# I2C-Level-Converter.net
KiCad netlist of a schematic drawn in EAGLE
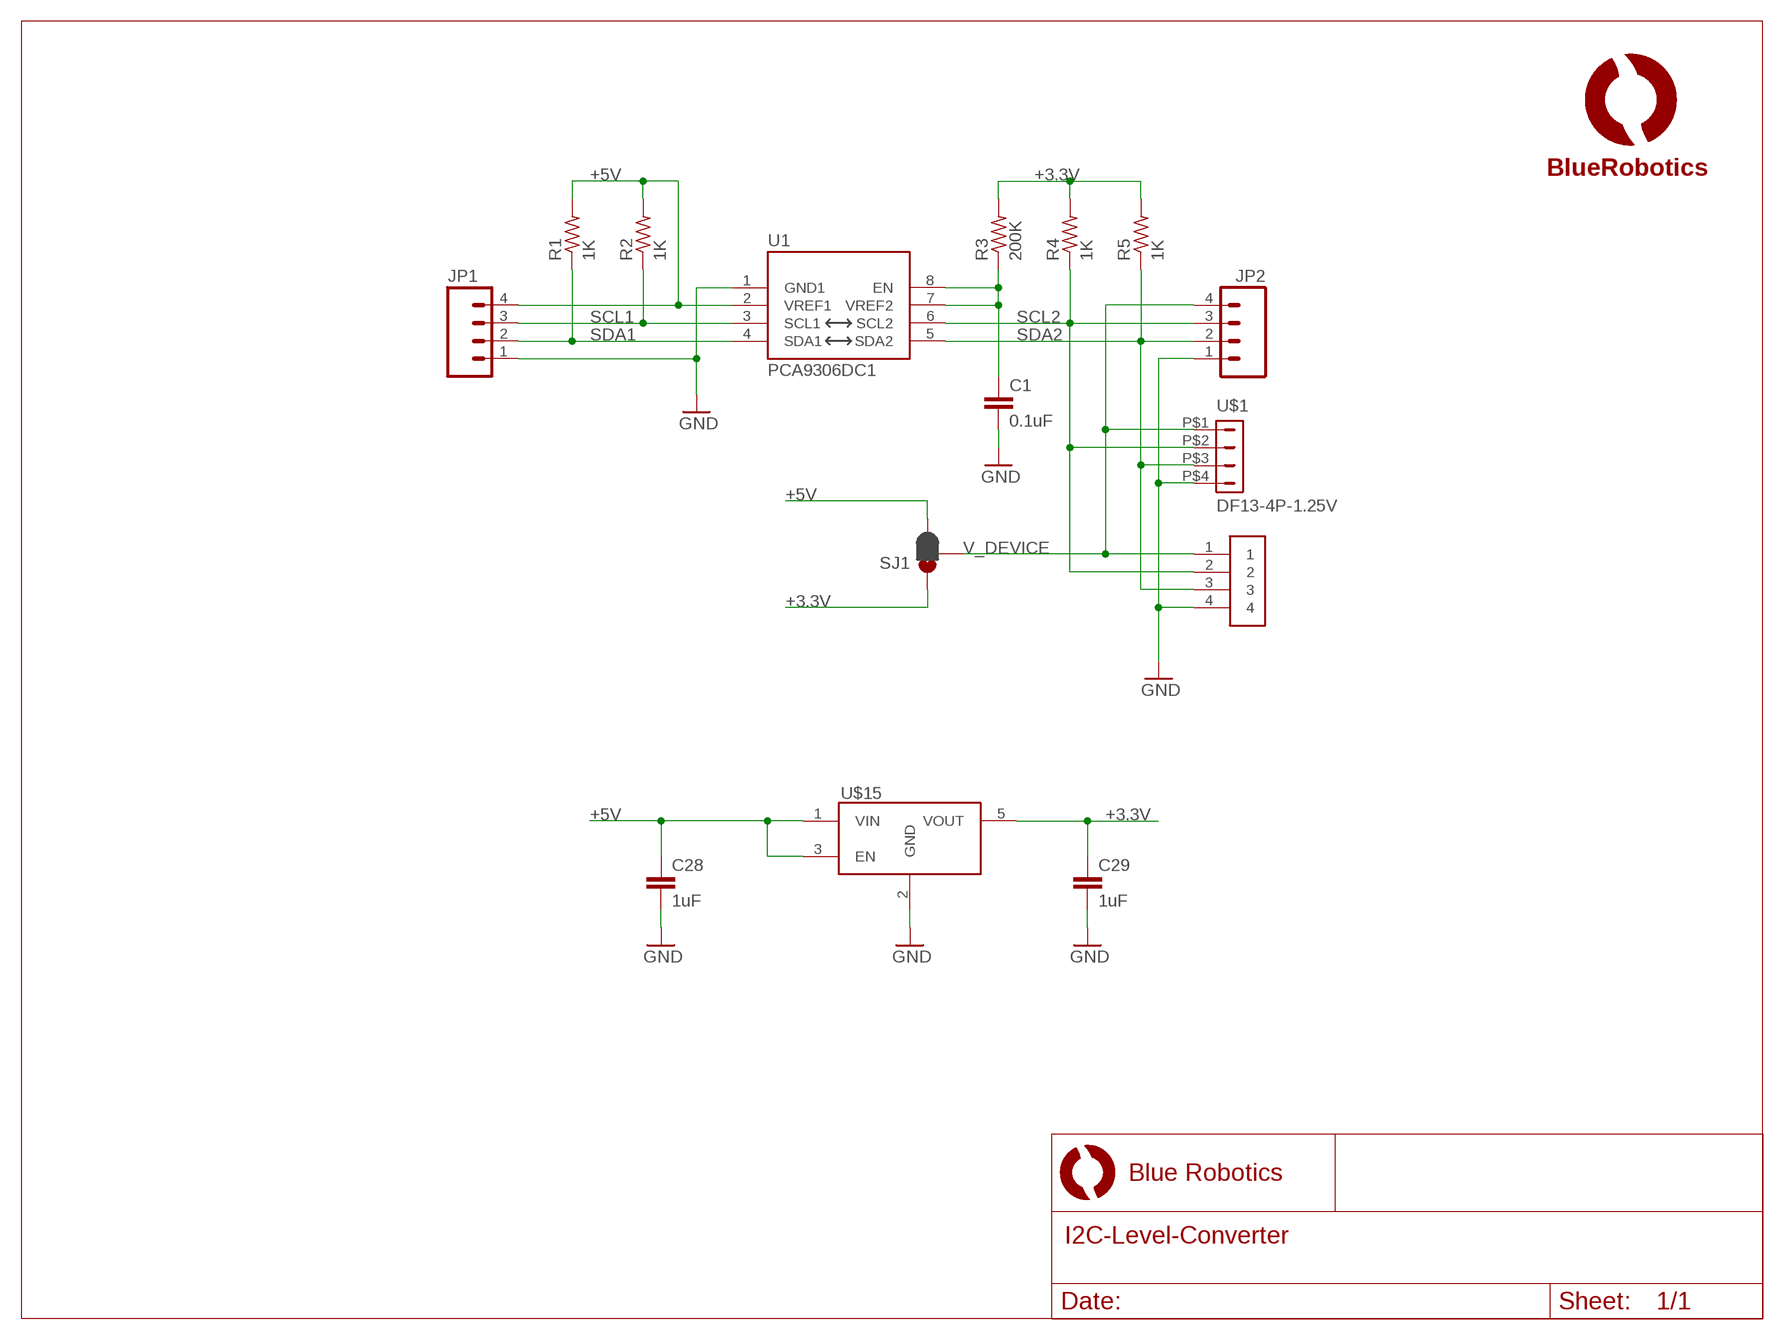
[diagram p0: schematic, sheet 1]

(export (version "E")
  (design (tool "Eeschema 10.0.6"))
  (components
    (comp (ref "C1")
      (value "0.1uF")
      (footprint "eagle-import:C0603")
      (libsource (lib "eagle-import") (part "C-EUC0603"))
    )
    (comp (ref "C28")
      (value "1uF")
      (footprint "eagle-import:0603-CAP")
      (libsource (lib "eagle-import") (part "CAP0603-CAP"))
    )
    (comp (ref "C29")
      (value "1uF")
      (footprint "eagle-import:0603-CAP")
      (libsource (lib "eagle-import") (part "CAP0603-CAP"))
    )
    (comp (ref "JP1")
      (value "M04PTH")
      (footprint "eagle-import:1X04")
      (libsource (lib "eagle-import") (part "M04PTH"))
    )
    (comp (ref "JP2")
      (value "M04PTH")
      (footprint "eagle-import:1X04")
      (libsource (lib "eagle-import") (part "M04PTH"))
    )
    (comp (ref "R1")
      (value "1K")
      (footprint "eagle-import:R0603")
      (libsource (lib "eagle-import") (part "R-US_R0603"))
    )
    (comp (ref "R2")
      (value "1K")
      (footprint "eagle-import:R0603")
      (libsource (lib "eagle-import") (part "R-US_R0603"))
    )
    (comp (ref "R3")
      (value "200K")
      (footprint "eagle-import:R0603")
      (libsource (lib "eagle-import") (part "R-US_R0603"))
    )
    (comp (ref "R4")
      (value "1K")
      (footprint "eagle-import:R0603")
      (libsource (lib "eagle-import") (part "R-US_R0603"))
    )
    (comp (ref "R5")
      (value "1K")
      (footprint "eagle-import:R0603")
      (libsource (lib "eagle-import") (part "R-US_R0603"))
    )
    (comp (ref "SJ1")
      (value "JUMPER-PAD-3-2OF3_NC_BY_PASTE")
      (footprint "eagle-import:PAD-JUMPER-3-2OF3_NC_BY_PASTE_YES_SILK_FULL_BOX")
      (libsource (lib "eagle-import") (part "JUMPER-PAD-3-2OF3_NC_BY_PASTE"))
    )
    (comp (ref "U$1")
      (value "DF13-4P-1.25V")
      (footprint "eagle-import:DF13C-4P-1.25V")
      (libsource (lib "eagle-import") (part "DF13-4P-1.25V"))
    )
    (comp (ref "U$2")
      (value "JST-GH-4SMT")
      (footprint "eagle-import:JST-GH-TOP-4")
      (libsource (lib "eagle-import") (part "JST-GH-4SMT"))
    )
    (comp (ref "U$3")
      (value "LOGOBR-LOGO-S")
      (footprint "eagle-import:BR-LOGO-SMALL")
      (libsource (lib "eagle-import") (part "LOGOBR-LOGO-S"))
    )
    (comp (ref "U$15")
      (value "VREG-MIC5365")
      (footprint "eagle-import:SC70-5L")
      (libsource (lib "eagle-import") (part "VREG-MIC5365"))
    )
    (comp (ref "U1")
      (value "PCA9306DC1")
      (footprint "eagle-import:PSOP-8")
      (libsource (lib "eagle-import") (part "PCA9306"))
    )
  )
  (nets
    (net (code "1") (name "/+3.3V") (class "Default")
      (node (ref "C29") (pin "1") (pinfunction "1_1") (pintype "passive"))
      (node (ref "R3") (pin "2") (pinfunction "2_2") (pintype "passive"))
      (node (ref "R4") (pin "2") (pinfunction "2_2") (pintype "passive"))
      (node (ref "R5") (pin "2") (pinfunction "2_2") (pintype "passive"))
      (node (ref "SJ1") (pin "1") (pinfunction "1_1") (pintype "passive"))
      (node (ref "U$15") (pin "5") (pinfunction "VOUT_5") (pintype "bidirectional"))
    )
    (net (code "2") (name "/+5V") (class "Default")
      (node (ref "C28") (pin "1") (pinfunction "1_1") (pintype "passive"))
      (node (ref "JP1") (pin "4") (pinfunction "4_4") (pintype "passive"))
      (node (ref "R1") (pin "2") (pinfunction "2_2") (pintype "passive"))
      (node (ref "R2") (pin "2") (pinfunction "2_2") (pintype "passive"))
      (node (ref "SJ1") (pin "3") (pinfunction "3_3") (pintype "passive"))
      (node (ref "U$15") (pin "1") (pinfunction "VIN_1") (pintype "bidirectional"))
      (node (ref "U$15") (pin "3") (pinfunction "EN_3") (pintype "bidirectional"))
      (node (ref "U1") (pin "2") (pinfunction "VREF1_2") (pintype "bidirectional"))
    )
    (net (code "3") (name "/SCL1") (class "Default")
      (node (ref "JP1") (pin "3") (pinfunction "3_3") (pintype "passive"))
      (node (ref "R2") (pin "1") (pinfunction "1_1") (pintype "passive"))
      (node (ref "U1") (pin "3") (pinfunction "SCL1_3") (pintype "bidirectional"))
    )
    (net (code "4") (name "/SCL2") (class "Default")
      (node (ref "JP2") (pin "3") (pinfunction "3_3") (pintype "passive"))
      (node (ref "R4") (pin "1") (pinfunction "1_1") (pintype "passive"))
      (node (ref "U$1") (pin "P$2") (pinfunction "2_P$2") (pintype "passive"))
      (node (ref "U$2") (pin "2") (pinfunction "2_2") (pintype "bidirectional"))
      (node (ref "U1") (pin "6") (pinfunction "SCL2_6") (pintype "bidirectional"))
    )
    (net (code "5") (name "/SDA1") (class "Default")
      (node (ref "JP1") (pin "2") (pinfunction "2_2") (pintype "passive"))
      (node (ref "R1") (pin "1") (pinfunction "1_1") (pintype "passive"))
      (node (ref "U1") (pin "4") (pinfunction "SDA1_4") (pintype "bidirectional"))
    )
    (net (code "6") (name "/SDA2") (class "Default")
      (node (ref "JP2") (pin "2") (pinfunction "2_2") (pintype "passive"))
      (node (ref "R5") (pin "1") (pinfunction "1_1") (pintype "passive"))
      (node (ref "U$1") (pin "P$3") (pinfunction "3_P$3") (pintype "passive"))
      (node (ref "U$2") (pin "3") (pinfunction "3_3") (pintype "bidirectional"))
      (node (ref "U1") (pin "5") (pinfunction "SDA2_5") (pintype "bidirectional"))
    )
    (net (code "7") (name "/V_DEVICE") (class "Default")
      (node (ref "JP2") (pin "4") (pinfunction "4_4") (pintype "passive"))
      (node (ref "SJ1") (pin "2") (pinfunction "2_2") (pintype "passive"))
      (node (ref "U$1") (pin "P$1") (pinfunction "1_P$1") (pintype "passive"))
      (node (ref "U$2") (pin "1") (pinfunction "1_1") (pintype "bidirectional"))
    )
    (net (code "8") (name "GND") (class "Default")
      (node (ref "C1") (pin "2") (pinfunction "2_2") (pintype "passive"))
      (node (ref "C28") (pin "2") (pinfunction "2_2") (pintype "passive"))
      (node (ref "C29") (pin "2") (pinfunction "2_2") (pintype "passive"))
      (node (ref "JP1") (pin "1") (pinfunction "1_1") (pintype "passive"))
      (node (ref "JP2") (pin "1") (pinfunction "1_1") (pintype "passive"))
      (node (ref "U$1") (pin "P$4") (pinfunction "4_P$4") (pintype "passive"))
      (node (ref "U$15") (pin "2") (pinfunction "GND_2") (pintype "bidirectional"))
      (node (ref "U$2") (pin "4") (pinfunction "4_4") (pintype "bidirectional"))
      (node (ref "U1") (pin "1") (pinfunction "GND1_1") (pintype "bidirectional"))
    )
    (net (code "9") (name "Net-(U1-EN)") (class "Default")
      (node (ref "C1") (pin "1") (pinfunction "1_1") (pintype "passive"))
      (node (ref "R3") (pin "1") (pinfunction "1_1") (pintype "passive"))
      (node (ref "U1") (pin "7") (pinfunction "VREF2_7") (pintype "bidirectional"))
      (node (ref "U1") (pin "8") (pinfunction "EN_8") (pintype "bidirectional"))
    )
  )
)
